# Programmer.net
KiCad netlist of a schematic drawn in Altium Designer
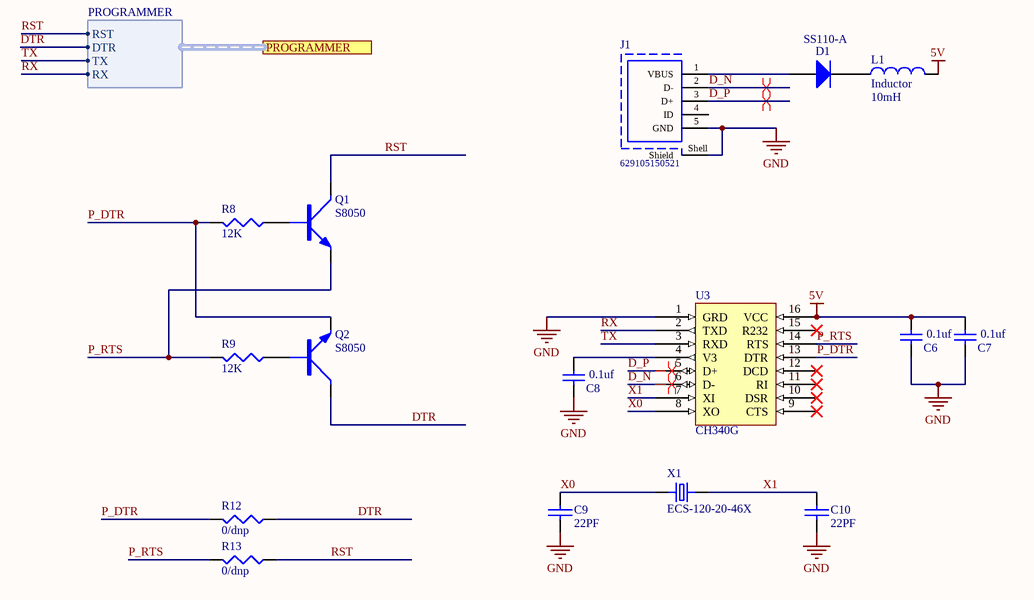
[diagram p0: Programmer.SchDoc]

(export (version "E")
  (design (tool "Eeschema 10.0.6"))
  (components
    (comp (ref "C6")
      (value "0.1uf")
      (footprint "CAPC0603")
      (fields
        (field (name "PART NUMBER") "08055C104KAJ2A")
        (field (name "MANUFACTURER") "AVX Interconnect / Elco")
      )
      (libsource (lib "Miscellaneous Devices") (part "CAP"))
    )
    (comp (ref "C7")
      (value "0.1uf")
      (footprint "CAPC0603")
      (fields
        (field (name "PART NUMBER") "08055C104KAJ2A")
        (field (name "MANUFACTURER") "AVX Interconnect / Elco")
      )
      (libsource (lib "Miscellaneous Devices") (part "CAP"))
    )
    (comp (ref "C8")
      (value "0.1uf")
      (footprint "CAPC0603")
      (fields
        (field (name "PART NUMBER") "08055C104KAJ2A")
        (field (name "MANUFACTURER") "AVX Interconnect / Elco")
      )
      (libsource (lib "Miscellaneous Devices") (part "CAP"))
    )
    (comp (ref "C9") (value "22PF") (footprint "CAPC0603") (libsource (lib "Devices") (part "CAP NP")))
    (comp (ref "C10") (value "22PF") (footprint "CAPC0603") (libsource (lib "Devices") (part "CAP NP")))
    (comp (ref "D1")
      (value "SS110-A")
      (footprint "BZT55B13GS08")
      (description "Default Diode")
      (fields (field (name "PUBLISHER") "Altium Limited"))
      (libsource (lib "Miscellaneous Devices") (part "Diode"))
    )
    (comp (ref "J1")
      (value "629105150521")
      (footprint "629105150521")
      (description "Micro USB 2.0 Type B Receptacle WR-COM, Horizontal, SMT, with Pegs, High Current at Pin 1 & Pin 5")
      (fields (field (name "MANUFACTURER") "Wurth Elektronik") (field (name "PUBLISHER") "WurthElektronik"))
      (libsource (lib "Altium Content Vault") (part "WE-USB-5-1SHLD"))
    )
    (comp (ref "L1")
      (value "Inductor")
      (footprint "CAPC0805")
      (fields (field (name "ALTIUM_VALUE") "10mH") (field (name "PUBLISHER") "Altium Limited"))
      (libsource (lib "Miscellaneous Devices") (part "Inductor"))
    )
    (comp (ref "Q1") (value "S8050") (footprint "SOT23-3") (libsource (lib "Devices") (part "NPN BEC")))
    (comp (ref "Q2") (value "S8050") (footprint "SOT23-3") (libsource (lib "Devices") (part "NPN BEC")))
    (comp (ref "R8")
      (value "12K")
      (footprint "RESC0603")
      (description "RESISTOR")
      (libsource (lib "Devices") (part "RES1"))
    )
    (comp (ref "R9")
      (value "12K")
      (footprint "RESC0603")
      (description "RESISTOR")
      (libsource (lib "Devices") (part "RES1"))
    )
    (comp (ref "R12")
      (value "0/dnp")
      (footprint "RESC0603")
      (description "RESISTOR")
      (libsource (lib "Devices") (part "RES1"))
    )
    (comp (ref "R13")
      (value "0/dnp")
      (footprint "RESC0603")
      (description "RESISTOR")
      (libsource (lib "Devices") (part "RES1"))
    )
    (comp (ref "U3")
      (value "CH340G")
      (footprint "SOIC16_N")
      (libsource (lib "CH340.Schlib1") (part "CH340G"))
    )
    (comp (ref "X1")
      (value "ECS-120-20-46X")
      (footprint "SnapEDApcb:XTAL_ECS-120-20-46X")
      (description "QUARTZ CRYSTAL  T/H")
      (libsource (lib "SnapEDAsch") (part "ECS-120-20-46X"))
    )
  )
  (nets
    (net (code "2") (name "/DTR") (class "Default")
      (node (ref "Q2") (pin "3") (pinfunction "COLL_3") (pintype "passive"))
      (node (ref "R12") (pin "1") (pintype "passive"))
    )
    (net (code "3") (name "/D_N") (class "Default")
      (node (ref "J1") (pin "2") (pinfunction "D-_2") (pintype "passive"))
      (node (ref "U3") (pin "6") (pinfunction "D-_6") (pintype "bidirectional"))
    )
    (net (code "4") (name "/D_P") (class "Default")
      (node (ref "J1") (pin "3") (pinfunction "D+_3") (pintype "passive"))
      (node (ref "U3") (pin "5") (pinfunction "D+_5") (pintype "bidirectional"))
    )
    (net (code "5") (name "/P_DTR") (class "Default")
      (node (ref "Q2") (pin "2") (pinfunction "EMIT_2") (pintype "passive"))
      (node (ref "R12") (pin "2") (pintype "passive"))
      (node (ref "R8") (pin "2") (pintype "passive"))
      (node (ref "U3") (pin "13") (pinfunction "DTR_13") (pintype "input"))
    )
    (net (code "6") (name "/P_RTS") (class "Default")
      (node (ref "Q1") (pin "2") (pinfunction "EMIT_2") (pintype "passive"))
      (node (ref "R13") (pin "2") (pintype "passive"))
      (node (ref "R9") (pin "2") (pintype "passive"))
      (node (ref "U3") (pin "14") (pinfunction "RTS_14") (pintype "input"))
    )
    (net (code "7") (name "/RST") (class "Default")
      (node (ref "Q1") (pin "3") (pinfunction "COLL_3") (pintype "passive"))
      (node (ref "R13") (pin "1") (pintype "passive"))
    )
    (net (code "8") (name "/RX") (class "Default")
      (node (ref "U3") (pin "2") (pinfunction "TXD_2") (pintype "output"))
    )
    (net (code "9") (name "/TX") (class "Default")
      (node (ref "U3") (pin "3") (pinfunction "RXD_3") (pintype "input"))
    )
    (net (code "10") (name "/X0") (class "Default")
      (node (ref "C9") (pin "2") (pintype "passive"))
      (node (ref "U3") (pin "8") (pinfunction "XO_8") (pintype "input"))
      (node (ref "X1") (pin "1") (pinfunction "1_1") (pintype "passive"))
    )
    (net (code "11") (name "/X1") (class "Default")
      (node (ref "C10") (pin "2") (pintype "passive"))
      (node (ref "U3") (pin "7") (pinfunction "XI_7") (pintype "input"))
      (node (ref "X1") (pin "2") (pinfunction "2_2") (pintype "passive"))
    )
    (net (code "13") (name "5V") (class "Default")
      (node (ref "C6") (pin "1") (pinfunction "1_1") (pintype "passive"))
      (node (ref "C7") (pin "1") (pinfunction "1_1") (pintype "passive"))
      (node (ref "L1") (pin "2") (pinfunction "2_2") (pintype "passive"))
      (node (ref "U3") (pin "16") (pinfunction "VCC_16") (pintype "input"))
    )
    (net (code "14") (name "GND") (class "Default")
      (node (ref "C10") (pin "1") (pintype "passive"))
      (node (ref "C6") (pin "2") (pinfunction "2_2") (pintype "passive"))
      (node (ref "C7") (pin "2") (pinfunction "2_2") (pintype "passive"))
      (node (ref "C8") (pin "2") (pinfunction "2_2") (pintype "passive"))
      (node (ref "C9") (pin "1") (pintype "passive"))
      (node (ref "J1") (pin "5") (pinfunction "GND_5") (pintype "passive"))
      (node (ref "J1") (pin "Shell") (pinfunction "Shield_Shell") (pintype "passive"))
      (node (ref "U3") (pin "1") (pinfunction "GRD_1") (pintype "input"))
    )
    (net (code "15") (name "Net-(D1-A)") (class "Default")
      (node (ref "D1") (pin "1") (pinfunction "A_1") (pintype "passive"))
      (node (ref "L1") (pin "1") (pinfunction "1_1") (pintype "passive"))
    )
    (net (code "16") (name "Net-(D1-K)") (class "Default")
      (node (ref "D1") (pin "2") (pinfunction "K_2") (pintype "passive"))
      (node (ref "J1") (pin "1") (pinfunction "VBUS_1") (pintype "passive"))
    )
    (net (code "17") (name "Net-(Q1-BASE)") (class "Default")
      (node (ref "Q1") (pin "1") (pinfunction "BASE_1") (pintype "passive"))
      (node (ref "R8") (pin "1") (pintype "passive"))
    )
    (net (code "18") (name "Net-(Q2-BASE)") (class "Default")
      (node (ref "Q2") (pin "1") (pinfunction "BASE_1") (pintype "passive"))
      (node (ref "R9") (pin "1") (pintype "passive"))
    )
    (net (code "19") (name "Net-(U3-V3)") (class "Default")
      (node (ref "C8") (pin "1") (pinfunction "1_1") (pintype "passive"))
      (node (ref "U3") (pin "4") (pinfunction "V3_4") (pintype "output"))
    )
    (net (code "20") (name "unconnected-(J1-ID-Pad4)") (class "Default")
      (node (ref "J1") (pin "4") (pinfunction "ID_4") (pintype "passive"))
    )
    (net (code "21") (name "unconnected-(U3-CTS-Pad9)") (class "Default")
      (node (ref "U3") (pin "9") (pinfunction "CTS_9") (pintype "input+no_connect"))
    )
    (net (code "22") (name "unconnected-(U3-DCD-Pad12)") (class "Default")
      (node (ref "U3") (pin "12") (pinfunction "DCD_12") (pintype "input+no_connect"))
    )
    (net (code "23") (name "unconnected-(U3-DSR-Pad10)") (class "Default")
      (node (ref "U3") (pin "10") (pinfunction "DSR_10") (pintype "input+no_connect"))
    )
    (net (code "24") (name "unconnected-(U3-R232-Pad15)") (class "Default")
      (node (ref "U3") (pin "15") (pinfunction "R232_15") (pintype "input+no_connect"))
    )
    (net (code "25") (name "unconnected-(U3-RI-Pad11)") (class "Default")
      (node (ref "U3") (pin "11") (pinfunction "RI_11") (pintype "input+no_connect"))
    )
  )
)
